# Main.net
KiCad netlist of a schematic drawn in Altium Designer
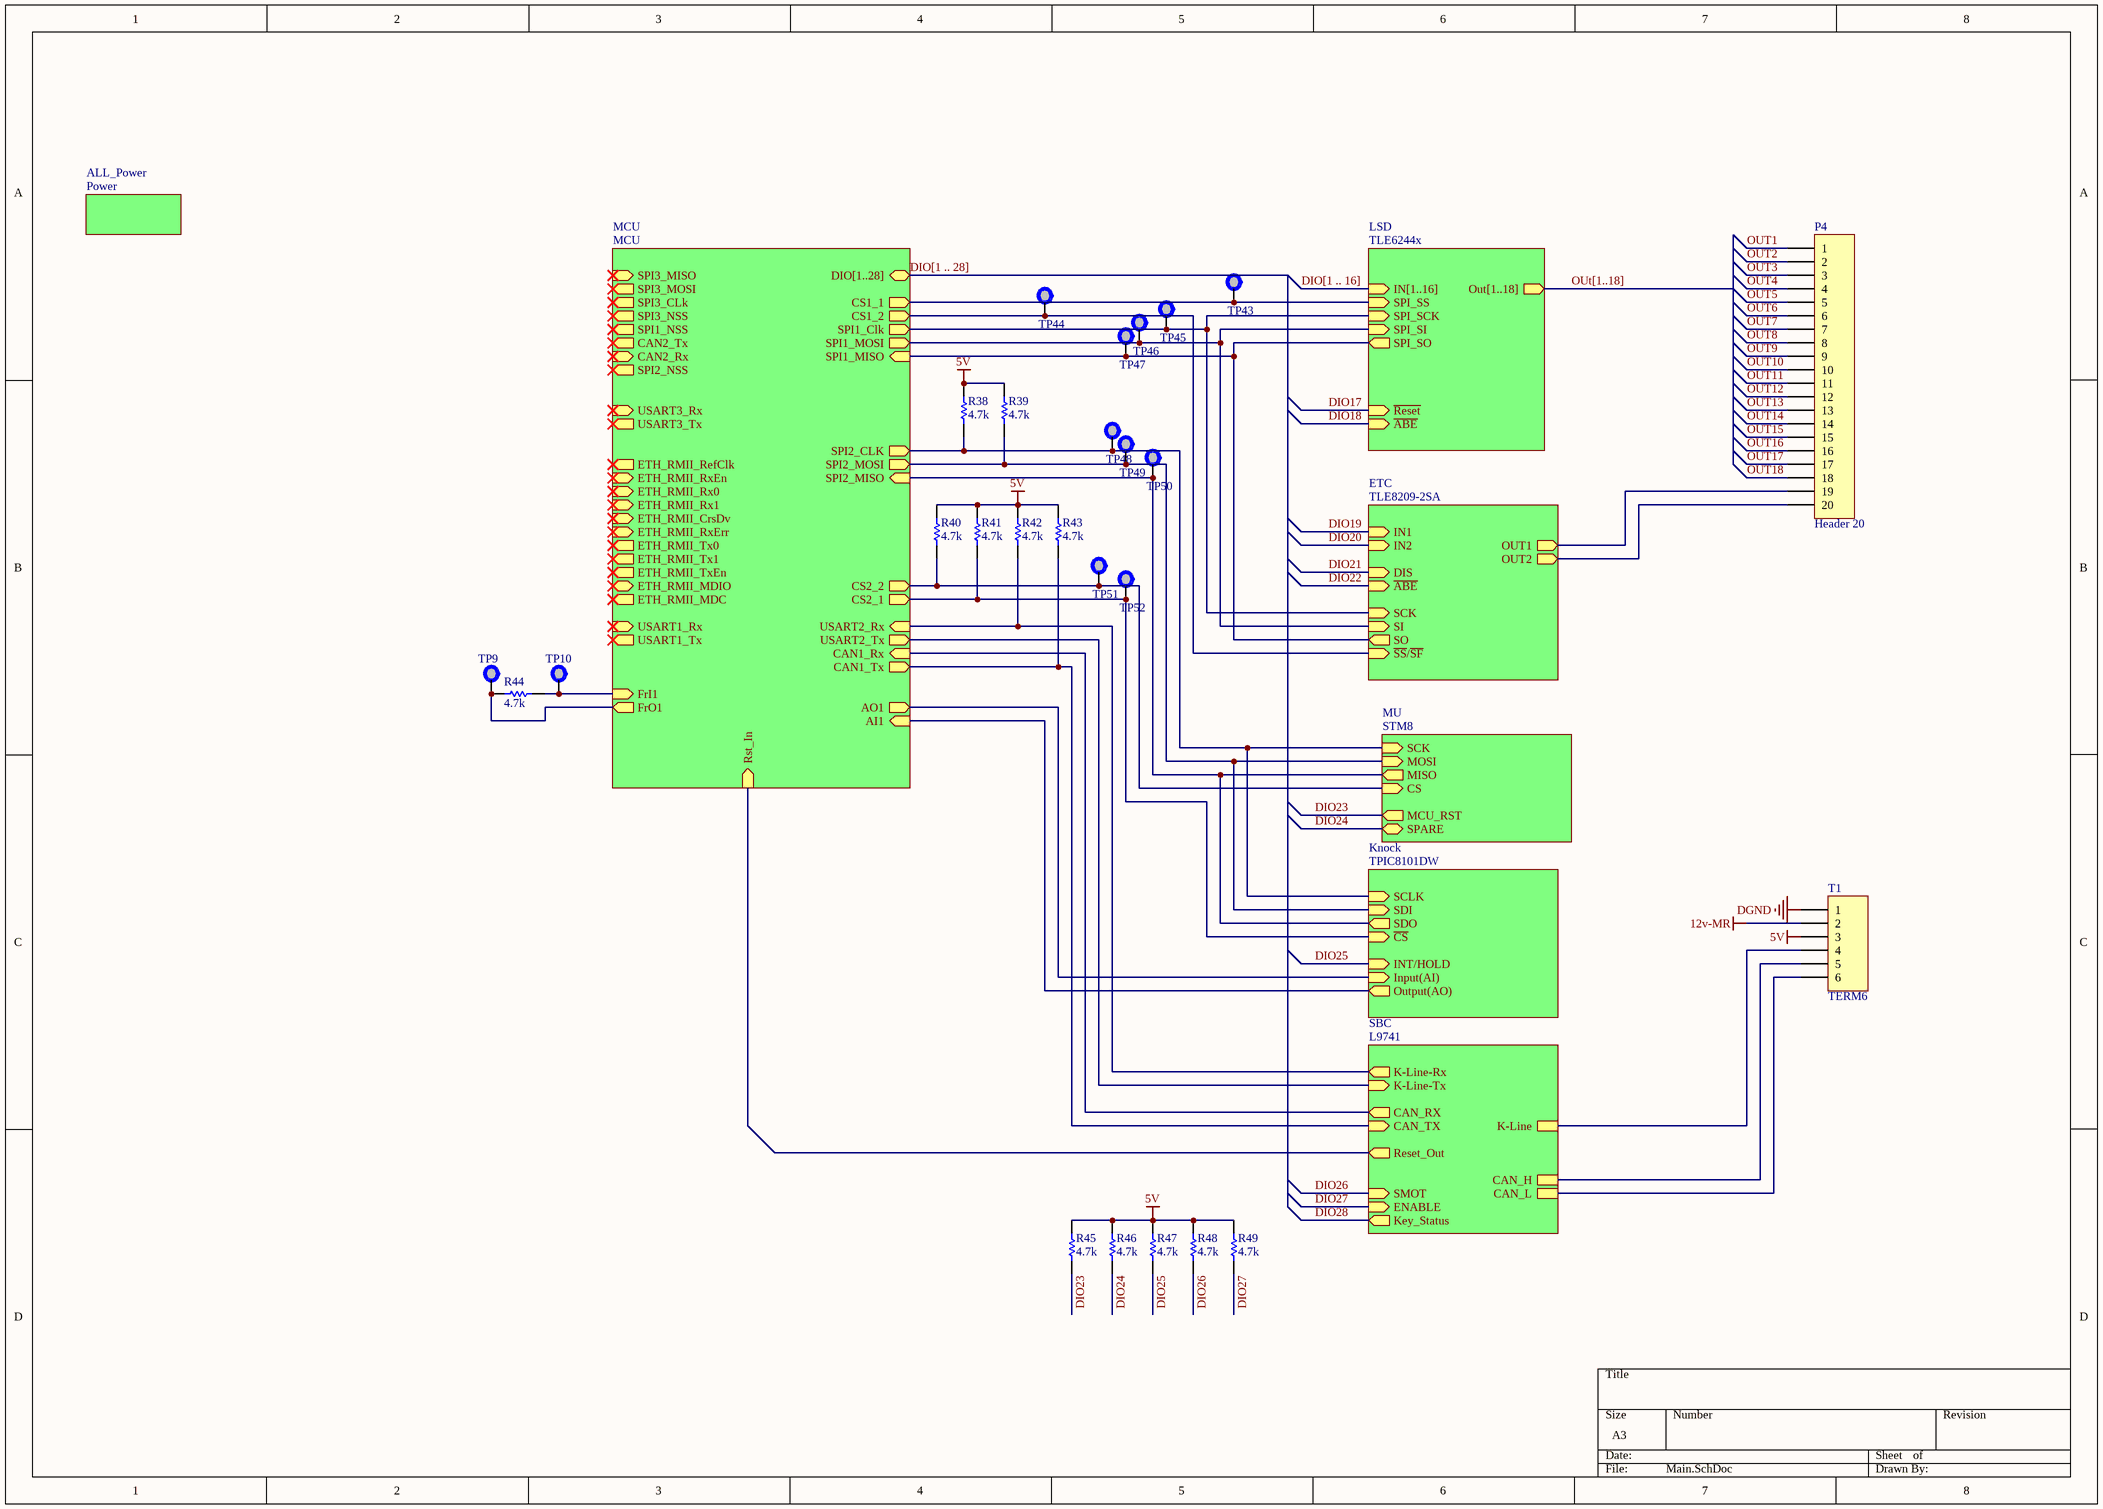
[diagram p0: Main.SchDoc]

(export (version "E")
  (design (tool "Eeschema 10.0.6"))
  (components
    (comp (ref "P4")
      (value "Header 20")
      (footprint "HDR1X20")
      (description "Header, 20-Pin")
      (fields (field (name "PUBLISHER") "Altium Limited"))
      (libsource (lib "Miscellaneous Connectors") (part "Header 20"))
    )
    (comp (ref "R38")
      (value "4.7k")
      (footprint "0805")
      (description "Resistor")
      (fields (field (name "Comment") "4.7K") (field (name "PUBLISHER") "Altium Limited"))
      (libsource (lib "Miscellaneous Devices") (part "Res1"))
    )
    (comp (ref "R39")
      (value "4.7k")
      (footprint "0805")
      (description "Resistor")
      (fields (field (name "Comment") "4.7K") (field (name "PUBLISHER") "Altium Limited"))
      (libsource (lib "Miscellaneous Devices") (part "Res1"))
    )
    (comp (ref "R40")
      (value "4.7k")
      (footprint "0805")
      (description "Resistor")
      (fields (field (name "Comment") "4.7K") (field (name "PUBLISHER") "Altium Limited"))
      (libsource (lib "Miscellaneous Devices") (part "Res1"))
    )
    (comp (ref "R41")
      (value "4.7k")
      (footprint "0805")
      (description "Resistor")
      (fields (field (name "Comment") "4.7K") (field (name "PUBLISHER") "Altium Limited"))
      (libsource (lib "Miscellaneous Devices") (part "Res1"))
    )
    (comp (ref "R42")
      (value "4.7k")
      (footprint "0805")
      (description "Resistor")
      (fields (field (name "Comment") "4.7K") (field (name "PUBLISHER") "Altium Limited"))
      (libsource (lib "Miscellaneous Devices") (part "Res1"))
    )
    (comp (ref "R43")
      (value "4.7k")
      (footprint "0805")
      (description "Resistor")
      (fields (field (name "Comment") "4.7K") (field (name "PUBLISHER") "Altium Limited"))
      (libsource (lib "Miscellaneous Devices") (part "Res1"))
    )
    (comp (ref "R44")
      (value "4.7k")
      (footprint "0805")
      (description "Resistor")
      (fields (field (name "Comment") "4.7K") (field (name "PUBLISHER") "Altium Limited"))
      (libsource (lib "Miscellaneous Devices") (part "Res1"))
    )
    (comp (ref "R45")
      (value "4.7k")
      (footprint "0805")
      (description "Resistor")
      (fields (field (name "Comment") "4.7K") (field (name "PUBLISHER") "Altium Limited"))
      (libsource (lib "Miscellaneous Devices") (part "Res1"))
    )
    (comp (ref "R46")
      (value "4.7k")
      (footprint "0805")
      (description "Resistor")
      (fields (field (name "Comment") "4.7K") (field (name "PUBLISHER") "Altium Limited"))
      (libsource (lib "Miscellaneous Devices") (part "Res1"))
    )
    (comp (ref "R47")
      (value "4.7k")
      (footprint "0805")
      (description "Resistor")
      (fields (field (name "Comment") "4.7K") (field (name "PUBLISHER") "Altium Limited"))
      (libsource (lib "Miscellaneous Devices") (part "Res1"))
    )
    (comp (ref "R48")
      (value "4.7k")
      (footprint "0805")
      (description "Resistor")
      (fields (field (name "Comment") "4.7K") (field (name "PUBLISHER") "Altium Limited"))
      (libsource (lib "Miscellaneous Devices") (part "Res1"))
    )
    (comp (ref "R49")
      (value "4.7k")
      (footprint "0805")
      (description "Resistor")
      (fields (field (name "Comment") "4.7K") (field (name "PUBLISHER") "Altium Limited"))
      (libsource (lib "Miscellaneous Devices") (part "Res1"))
    )
    (comp (ref "T1")
      (value "TERM6")
      (footprint "TERM6")
      (description "Header, 6-Pin")
      (fields (field (name "PUBLISHER") "Altium Limited"))
      (libsource (lib "Miscellaneous Connectors") (part "MHDR1X6"))
    )
    (comp (ref "TP9") (value "TestPoint") (footprint "TP") (libsource (lib "SchlibV0.1") (part "TestPoint")))
    (comp (ref "TP10") (value "TestPoint") (footprint "TP") (libsource (lib "SchlibV0.1") (part "TestPoint")))
    (comp (ref "TP43") (value "TestPoint") (footprint "TP") (libsource (lib "SchlibV0.1") (part "TestPoint")))
    (comp (ref "TP44") (value "TestPoint") (footprint "TP") (libsource (lib "SchlibV0.1") (part "TestPoint")))
    (comp (ref "TP45") (value "TestPoint") (footprint "TP") (libsource (lib "SchlibV0.1") (part "TestPoint")))
    (comp (ref "TP46") (value "TestPoint") (footprint "TP") (libsource (lib "SchlibV0.1") (part "TestPoint")))
    (comp (ref "TP47") (value "TestPoint") (footprint "TP") (libsource (lib "SchlibV0.1") (part "TestPoint")))
    (comp (ref "TP48") (value "TestPoint") (footprint "TP") (libsource (lib "SchlibV0.1") (part "TestPoint")))
    (comp (ref "TP49") (value "TestPoint") (footprint "TP") (libsource (lib "SchlibV0.1") (part "TestPoint")))
    (comp (ref "TP50") (value "TestPoint") (footprint "TP") (libsource (lib "SchlibV0.1") (part "TestPoint")))
    (comp (ref "TP51") (value "TestPoint") (footprint "TP") (libsource (lib "SchlibV0.1") (part "TestPoint")))
    (comp (ref "TP52") (value "TestPoint") (footprint "TP") (libsource (lib "SchlibV0.1") (part "TestPoint")))
  )
  (nets
    (net (code "22") (name "/CAN1_Tx") (class "Default")
      (node (ref "R43") (pin "1") (pinfunction "1_1") (pintype "passive"))
    )
    (net (code "25") (name "/CAN_H") (class "Default")
      (node (ref "T1") (pin "5") (pinfunction "5_5") (pintype "passive"))
    )
    (net (code "26") (name "/CAN_L") (class "Default")
      (node (ref "T1") (pin "6") (pinfunction "6_6") (pintype "passive"))
    )
    (net (code "28") (name "/CS1_1") (class "Default") (node (ref "TP43") (pin "1") (pintype "passive")))
    (net (code "29") (name "/CS1_2") (class "Default") (node (ref "TP44") (pin "1") (pintype "passive")))
    (net (code "30") (name "/CS2_1") (class "Default")
      (node (ref "R41") (pin "1") (pinfunction "1_1") (pintype "passive"))
      (node (ref "TP52") (pin "1") (pintype "passive"))
    )
    (net (code "31") (name "/CS2_2") (class "Default")
      (node (ref "R40") (pin "2") (pinfunction "2_2") (pintype "passive"))
      (node (ref "TP51") (pin "1") (pintype "passive"))
    )
    (net (code "38") (name "/DIO23") (class "Default")
      (node (ref "R45") (pin "2") (pinfunction "2_2") (pintype "passive"))
    )
    (net (code "39") (name "/DIO24") (class "Default")
      (node (ref "R46") (pin "2") (pinfunction "2_2") (pintype "passive"))
    )
    (net (code "40") (name "/DIO25") (class "Default")
      (node (ref "R47") (pin "2") (pinfunction "2_2") (pintype "passive"))
    )
    (net (code "41") (name "/DIO26") (class "Default")
      (node (ref "R48") (pin "2") (pinfunction "2_2") (pintype "passive"))
    )
    (net (code "42") (name "/DIO27") (class "Default")
      (node (ref "R49") (pin "2") (pinfunction "2_2") (pintype "passive"))
    )
    (net (code "55") (name "/FrI1") (class "Default")
      (node (ref "R44") (pin "2") (pinfunction "2_2") (pintype "passive"))
      (node (ref "TP10") (pin "1") (pintype "passive"))
    )
    (net (code "56") (name "/FrO1") (class "Default")
      (node (ref "R44") (pin "1") (pinfunction "1_1") (pintype "passive"))
      (node (ref "TP9") (pin "1") (pintype "passive"))
    )
    (net (code "57") (name "/K-Line") (class "Default")
      (node (ref "T1") (pin "4") (pinfunction "4_4") (pintype "passive"))
    )
    (net (code "58") (name "/K-Line-Rx") (class "Default")
      (node (ref "R42") (pin "1") (pinfunction "1_1") (pintype "passive"))
    )
    (net (code "59") (name "/MISO") (class "Default") (node (ref "TP50") (pin "1") (pintype "passive")))
    (net (code "60") (name "/OUT1") (class "Default")
      (node (ref "P4") (pin "1") (pinfunction "1_1") (pintype "passive"))
    )
    (net (code "61") (name "/OUT1_1") (class "Default")
      (node (ref "P4") (pin "19") (pinfunction "19_19") (pintype "passive"))
    )
    (net (code "62") (name "/OUT2") (class "Default")
      (node (ref "P4") (pin "2") (pinfunction "2_2") (pintype "passive"))
    )
    (net (code "63") (name "/OUT2_1") (class "Default")
      (node (ref "P4") (pin "20") (pinfunction "20_20") (pintype "passive"))
    )
    (net (code "64") (name "/OUT3") (class "Default")
      (node (ref "P4") (pin "3") (pinfunction "3_3") (pintype "passive"))
    )
    (net (code "65") (name "/OUT4") (class "Default")
      (node (ref "P4") (pin "4") (pinfunction "4_4") (pintype "passive"))
    )
    (net (code "66") (name "/OUT5") (class "Default")
      (node (ref "P4") (pin "5") (pinfunction "5_5") (pintype "passive"))
    )
    (net (code "67") (name "/OUT6") (class "Default")
      (node (ref "P4") (pin "6") (pinfunction "6_6") (pintype "passive"))
    )
    (net (code "68") (name "/OUT7") (class "Default")
      (node (ref "P4") (pin "7") (pinfunction "7_7") (pintype "passive"))
    )
    (net (code "69") (name "/OUT8") (class "Default")
      (node (ref "P4") (pin "8") (pinfunction "8_8") (pintype "passive"))
    )
    (net (code "70") (name "/OUT9") (class "Default")
      (node (ref "P4") (pin "9") (pinfunction "9_9") (pintype "passive"))
    )
    (net (code "71") (name "/OUT10") (class "Default")
      (node (ref "P4") (pin "10") (pinfunction "10_10") (pintype "passive"))
    )
    (net (code "72") (name "/OUT11") (class "Default")
      (node (ref "P4") (pin "11") (pinfunction "11_11") (pintype "passive"))
    )
    (net (code "73") (name "/OUT12") (class "Default")
      (node (ref "P4") (pin "12") (pinfunction "12_12") (pintype "passive"))
    )
    (net (code "74") (name "/OUT13") (class "Default")
      (node (ref "P4") (pin "13") (pinfunction "13_13") (pintype "passive"))
    )
    (net (code "75") (name "/OUT14") (class "Default")
      (node (ref "P4") (pin "14") (pinfunction "14_14") (pintype "passive"))
    )
    (net (code "76") (name "/OUT15") (class "Default")
      (node (ref "P4") (pin "15") (pinfunction "15_15") (pintype "passive"))
    )
    (net (code "77") (name "/OUT16") (class "Default")
      (node (ref "P4") (pin "16") (pinfunction "16_16") (pintype "passive"))
    )
    (net (code "78") (name "/OUT17") (class "Default")
      (node (ref "P4") (pin "17") (pinfunction "17_17") (pintype "passive"))
    )
    (net (code "79") (name "/OUT18") (class "Default")
      (node (ref "P4") (pin "18") (pinfunction "18_18") (pintype "passive"))
    )
    (net (code "83") (name "/SO") (class "Default") (node (ref "TP47") (pin "1") (pintype "passive")))
    (net (code "84") (name "/SPI1_Clk") (class "Default") (node (ref "TP45") (pin "1") (pintype "passive")))
    (net (code "85") (name "/SPI1_MOSI") (class "Default") (node (ref "TP46") (pin "1") (pintype "passive")))
    (net (code "87") (name "/SPI2_CLK") (class "Default")
      (node (ref "R38") (pin "1") (pinfunction "1_1") (pintype "passive"))
      (node (ref "TP48") (pin "1") (pintype "passive"))
    )
    (net (code "88") (name "/SPI2_MOSI") (class "Default")
      (node (ref "R39") (pin "1") (pinfunction "1_1") (pintype "passive"))
      (node (ref "TP49") (pin "1") (pintype "passive"))
    )
    (net (code "101") (name "5V") (class "Default")
      (node (ref "R38") (pin "2") (pinfunction "2_2") (pintype "passive"))
      (node (ref "R39") (pin "2") (pinfunction "2_2") (pintype "passive"))
      (node (ref "R40") (pin "1") (pinfunction "1_1") (pintype "passive"))
      (node (ref "R41") (pin "2") (pinfunction "2_2") (pintype "passive"))
      (node (ref "R42") (pin "2") (pinfunction "2_2") (pintype "passive"))
      (node (ref "R43") (pin "2") (pinfunction "2_2") (pintype "passive"))
      (node (ref "R45") (pin "1") (pinfunction "1_1") (pintype "passive"))
      (node (ref "R46") (pin "1") (pinfunction "1_1") (pintype "passive"))
      (node (ref "R47") (pin "1") (pinfunction "1_1") (pintype "passive"))
      (node (ref "R48") (pin "1") (pinfunction "1_1") (pintype "passive"))
      (node (ref "R49") (pin "1") (pinfunction "1_1") (pintype "passive"))
      (node (ref "T1") (pin "3") (pinfunction "3_3") (pintype "passive"))
    )
    (net (code "102") (name "12v-MR") (class "Default")
      (node (ref "T1") (pin "2") (pinfunction "2_2") (pintype "passive"))
    )
    (net (code "103") (name "DGND") (class "Default")
      (node (ref "T1") (pin "1") (pinfunction "1_1") (pintype "passive"))
    )
  )
)
